# PowerManager.net
KiCad netlist of a schematic drawn in Altium Designer
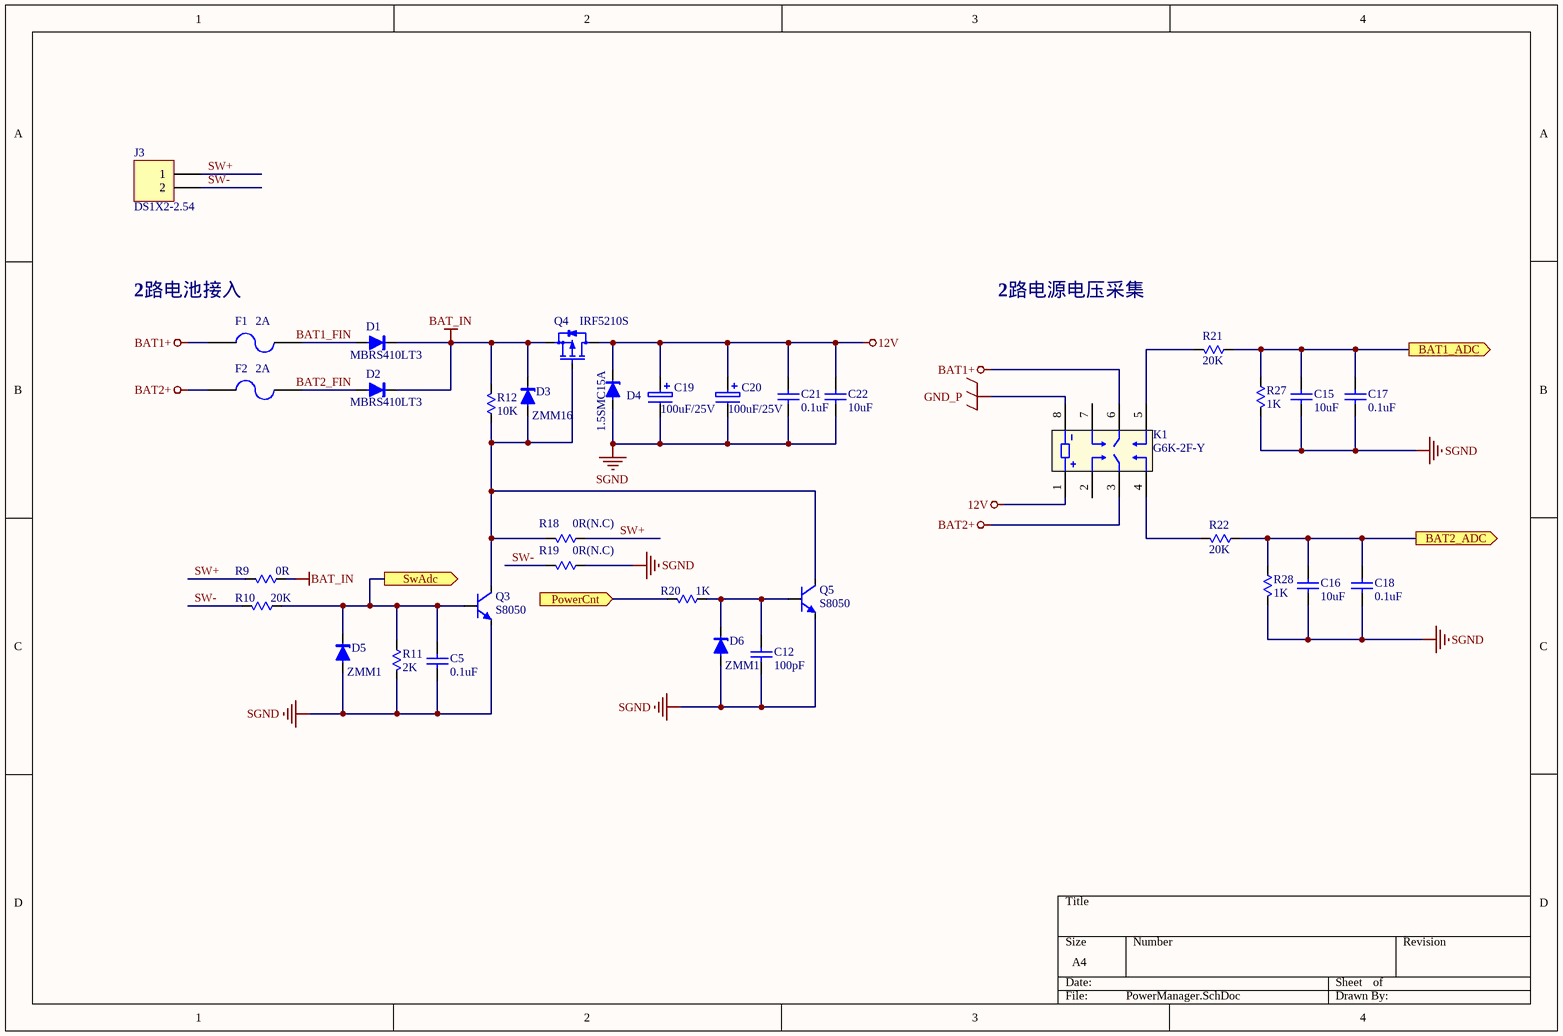
[diagram p0: PowerManager.SchDoc]

(export (version "E")
  (design (tool "Eeschema 10.0.6"))
  (components
    (comp (ref "C5")
      (value "0.1uF")
      (footprint "C0805")
      (description "Capacitor")
      (fields (field (name "PUBLISHER") "Altium Limited"))
      (libsource (lib "Miscellaneous Devices") (part "Cap"))
    )
    (comp (ref "C12")
      (value "100pF")
      (footprint "C0805")
      (description "Capacitor")
      (fields (field (name "PUBLISHER") "Altium Limited"))
      (libsource (lib "Miscellaneous Devices") (part "Cap"))
    )
    (comp (ref "C15")
      (value "10uF")
      (footprint "C0805")
      (description "CAP")
      (fields (field (name "PUBLISHER") "Altium Limited"))
      (libsource (lib "Passive Components Class") (part "CAP"))
    )
    (comp (ref "C16")
      (value "10uF")
      (footprint "C0805")
      (description "CAP")
      (fields (field (name "PUBLISHER") "Altium Limited"))
      (libsource (lib "Passive Components Class") (part "CAP"))
    )
    (comp (ref "C17")
      (value "0.1uF")
      (footprint "C0805")
      (description "CAP")
      (fields (field (name "PUBLISHER") "Altium Limited"))
      (libsource (lib "Passive Components Class") (part "CAP"))
    )
    (comp (ref "C18")
      (value "0.1uF")
      (footprint "C0805")
      (description "CAP")
      (fields (field (name "PUBLISHER") "Altium Limited"))
      (libsource (lib "Passive Components Class") (part "CAP"))
    )
    (comp (ref "C19")
      (value "100uF/25V")
      (footprint "CT7343-E-S")
      (description "Electrolytic Capacitor")
      (libsource (lib "*") (part "ELECTRO"))
    )
    (comp (ref "C20")
      (value "100uF/25V")
      (footprint "CT7343-E-S")
      (description "Electrolytic Capacitor")
      (libsource (lib "*") (part "ELECTRO"))
    )
    (comp (ref "C21")
      (value "0.1uF")
      (footprint "C0805")
      (description "Capacitor")
      (fields (field (name "PUBLISHER") "Altium Limited"))
      (libsource (lib "Miscellaneous Devices") (part "Cap"))
    )
    (comp (ref "C22")
      (value "10uF")
      (footprint "C0805")
      (description "Capacitor")
      (fields (field (name "PUBLISHER") "Altium Limited"))
      (libsource (lib "Miscellaneous Devices") (part "Cap"))
    )
    (comp (ref "D1")
      (value "MBRS410LT3")
      (footprint "SMC")
      (description "Small Signal Zener Diodes")
      (libsource (lib "Passive Components Class") (part "DIODE-ZENER"))
    )
    (comp (ref "D2")
      (value "MBRS410LT3")
      (footprint "SMC")
      (description "Small Signal Zener Diodes")
      (libsource (lib "Passive Components Class") (part "DIODE-ZENER"))
    )
    (comp (ref "D3")
      (value "ZMM16")
      (footprint "SOD-80")
      (description "Small Signal Zener Diodes")
      (libsource (lib "Passive Components Class") (part "DIODE-ZENER"))
    )
    (comp (ref "D4")
      (value "1.5SMC15A")
      (footprint "SMC")
      (description "Small Signal Zener Diodes")
      (libsource (lib "Passive Components Class") (part "DIODE-ZENER"))
    )
    (comp (ref "D5")
      (value "ZMM1")
      (footprint "SOD-80")
      (description "Small Signal Zener Diodes")
      (libsource (lib "Passive Components Class") (part "DIODE-ZENER"))
    )
    (comp (ref "D6")
      (value "ZMM1")
      (footprint "SOD-80")
      (description "Small Signal Zener Diodes")
      (libsource (lib "Passive Components Class") (part "DIODE-ZENER"))
    )
    (comp (ref "F1")
      (value "2A")
      (footprint "F1812")
      (description "Fuse")
      (libsource (lib "*") (part "FUSE2"))
    )
    (comp (ref "F2")
      (value "2A")
      (footprint "F1812")
      (description "Fuse")
      (libsource (lib "*") (part "FUSE2"))
    )
    (comp (ref "J3")
      (value "DS1X2-2.54")
      (footprint "ZH1X2WT-1.5")
      (description "Header, 2-Pin")
      (fields (field (name "PUBLISHER") "Altium Limited"))
      (libsource (lib "Miscellaneous Connectors") (part "Header 2"))
    )
    (comp (ref "K1")
      (value "G6K-2F-Y")
      (footprint "G6K-2F-Y")
      (libsource (lib "Productor Class") (part "G6K-2F-Y"))
    )
    (comp (ref "Q3")
      (value "S8050")
      (footprint "SOT-23")
      (description "NPN General Purpose Amplifier")
      (fields (field (name "PUBLISHER") "Altium Limited"))
      (libsource (lib "Bdmc4810") (part "NPN"))
    )
    (comp (ref "Q4")
      (value "IRF5210S")
      (footprint "TO-262")
      (description "P-Channel 30-V (D-S), 150 C MOSFET")
      (libsource (lib "Passive Components Class") (part "PMOS"))
    )
    (comp (ref "Q5")
      (value "S8050")
      (footprint "SOT-23")
      (description "NPN General Purpose Amplifier")
      (fields (field (name "PUBLISHER") "Altium Limited"))
      (libsource (lib "Bdmc4810") (part "NPN"))
    )
    (comp (ref "R9")
      (value "0R")
      (footprint "R0805")
      (description "Resistor")
      (fields (field (name "PUBLISHER") "Altium Limited"))
      (libsource (lib "Temp") (part "Res"))
    )
    (comp (ref "R10")
      (value "20K")
      (footprint "R0805")
      (description "Resistor")
      (fields (field (name "PUBLISHER") "Altium Limited"))
      (libsource (lib "Temp") (part "Res"))
    )
    (comp (ref "R11")
      (value "2K")
      (footprint "R0805")
      (description "Resistor")
      (fields (field (name "PUBLISHER") "Altium Limited"))
      (libsource (lib "Temp") (part "Res"))
    )
    (comp (ref "R12")
      (value "10K")
      (footprint "R0805")
      (description "Resistor")
      (fields (field (name "PUBLISHER") "Altium Limited"))
      (libsource (lib "Temp") (part "Res"))
    )
    (comp (ref "R18")
      (value "0R(N.C)")
      (footprint "R0805")
      (description "Resistor")
      (fields (field (name "PUBLISHER") "Altium Limited"))
      (libsource (lib "Passive Components Class") (part "RES"))
    )
    (comp (ref "R19")
      (value "0R(N.C)")
      (footprint "R0805")
      (description "Resistor")
      (fields (field (name "PUBLISHER") "Altium Limited"))
      (libsource (lib "Passive Components Class") (part "RES"))
    )
    (comp (ref "R20")
      (value "1K")
      (footprint "R0805")
      (description "Resistor")
      (fields (field (name "PUBLISHER") "Altium Limited"))
      (libsource (lib "Temp") (part "Res"))
    )
    (comp (ref "R21")
      (value "20K")
      (footprint "R0805")
      (description "Resistor")
      (fields (field (name "PUBLISHER") "Altium Limited"))
      (libsource (lib "") (part "RES_1"))
    )
    (comp (ref "R22")
      (value "20K")
      (footprint "R0805")
      (description "Resistor")
      (fields (field (name "PUBLISHER") "Altium Limited"))
      (libsource (lib "") (part "RES_1"))
    )
    (comp (ref "R27")
      (value "1K")
      (footprint "R0805")
      (description "Resistor")
      (fields (field (name "PUBLISHER") "Altium Limited"))
      (libsource (lib "") (part "RES_1"))
    )
    (comp (ref "R28")
      (value "1K")
      (footprint "R0805")
      (description "Resistor")
      (fields (field (name "PUBLISHER") "Altium Limited"))
      (libsource (lib "") (part "RES_1"))
    )
  )
  (nets
    (net (code "1") (name "/BAT1_ADC") (class "Default")
      (node (ref "C15") (pin "1") (pinfunction "1_1") (pintype "passive"))
      (node (ref "C17") (pin "1") (pinfunction "1_1") (pintype "passive"))
      (node (ref "R21") (pin "2") (pinfunction "2_2") (pintype "passive"))
      (node (ref "R27") (pin "2") (pinfunction "2_2") (pintype "passive"))
    )
    (net (code "3") (name "/BAT2_ADC") (class "Default")
      (node (ref "C16") (pin "1") (pinfunction "1_1") (pintype "passive"))
      (node (ref "C18") (pin "1") (pinfunction "1_1") (pintype "passive"))
      (node (ref "R22") (pin "2") (pinfunction "2_2") (pintype "passive"))
      (node (ref "R28") (pin "2") (pinfunction "2_2") (pintype "passive"))
    )
    (net (code "5") (name "/PowerCnt") (class "Default")
      (node (ref "R20") (pin "1") (pinfunction "1_1") (pintype "passive"))
    )
    (net (code "6") (name "/SW+") (class "Default")
      (node (ref "J3") (pin "1") (pinfunction "1_1") (pintype "passive"))
      (node (ref "R18") (pin "1") (pinfunction "1_1") (pintype "passive"))
      (node (ref "R9") (pin "1") (pinfunction "1_1") (pintype "passive"))
    )
    (net (code "7") (name "/SW-") (class "Default")
      (node (ref "J3") (pin "2") (pinfunction "2_2") (pintype "passive"))
      (node (ref "R10") (pin "1") (pinfunction "1_1") (pintype "passive"))
      (node (ref "R19") (pin "2") (pinfunction "2_2") (pintype "passive"))
    )
    (net (code "8") (name "/SwAdc") (class "Default")
      (node (ref "C5") (pin "2") (pinfunction "2_2") (pintype "passive"))
      (node (ref "D5") (pin "2") (pinfunction "K_2") (pintype "passive"))
      (node (ref "Q3") (pin "1") (pinfunction "B_1") (pintype "passive"))
      (node (ref "R10") (pin "2") (pinfunction "2_2") (pintype "passive"))
      (node (ref "R11") (pin "2") (pinfunction "2_2") (pintype "passive"))
    )
    (net (code "9") (name "12V") (class "Default")
      (node (ref "C19") (pin "1") (pinfunction "1_1") (pintype "passive"))
      (node (ref "C20") (pin "1") (pinfunction "1_1") (pintype "passive"))
      (node (ref "C21") (pin "2") (pinfunction "2_2") (pintype "passive"))
      (node (ref "C22") (pin "2") (pinfunction "2_2") (pintype "passive"))
      (node (ref "D4") (pin "2") (pinfunction "K_2") (pintype "passive"))
      (node (ref "K1") (pin "1") (pinfunction "1_1") (pintype "passive"))
      (node (ref "Q4") (pin "2") (pinfunction "D_2") (pintype "passive"))
    )
    (net (code "10") (name "BAT1+") (class "Default")
      (node (ref "F1") (pin "1") (pinfunction "1_1") (pintype "passive"))
      (node (ref "K1") (pin "6") (pinfunction "6_6") (pintype "passive"))
    )
    (net (code "11") (name "BAT2+") (class "Default")
      (node (ref "F2") (pin "1") (pinfunction "1_1") (pintype "passive"))
      (node (ref "K1") (pin "3") (pinfunction "3_3") (pintype "passive"))
    )
    (net (code "12") (name "BAT_IN") (class "Default")
      (node (ref "D1") (pin "2") (pinfunction "K_2") (pintype "passive"))
      (node (ref "D2") (pin "2") (pinfunction "K_2") (pintype "passive"))
      (node (ref "D3") (pin "2") (pinfunction "K_2") (pintype "passive"))
      (node (ref "Q4") (pin "3") (pinfunction "S_3") (pintype "passive"))
      (node (ref "R12") (pin "1") (pinfunction "1_1") (pintype "passive"))
      (node (ref "R9") (pin "2") (pinfunction "2_2") (pintype "passive"))
    )
    (net (code "13") (name "GND_P") (class "Default")
      (node (ref "K1") (pin "8") (pinfunction "8_8") (pintype "passive"))
    )
    (net (code "14") (name "Net-(D1-A)") (class "Default")
      (node (ref "D1") (pin "1") (pinfunction "A_1") (pintype "passive"))
      (node (ref "F1") (pin "2") (pinfunction "2_2") (pintype "passive"))
    )
    (net (code "15") (name "Net-(D2-A)") (class "Default")
      (node (ref "D2") (pin "1") (pinfunction "A_1") (pintype "passive"))
      (node (ref "F2") (pin "2") (pinfunction "2_2") (pintype "passive"))
    )
    (net (code "16") (name "Net-(D3-A)") (class "Default")
      (node (ref "D3") (pin "1") (pinfunction "A_1") (pintype "passive"))
      (node (ref "Q3") (pin "3") (pinfunction "C_3") (pintype "passive"))
      (node (ref "Q4") (pin "1") (pinfunction "G_1") (pintype "passive"))
      (node (ref "Q5") (pin "3") (pinfunction "C_3") (pintype "passive"))
      (node (ref "R12") (pin "2") (pinfunction "2_2") (pintype "passive"))
      (node (ref "R18") (pin "2") (pinfunction "2_2") (pintype "passive"))
    )
    (net (code "17") (name "Net-(D6-K)") (class "Default")
      (node (ref "C12") (pin "2") (pinfunction "2_2") (pintype "passive"))
      (node (ref "D6") (pin "2") (pinfunction "K_2") (pintype "passive"))
      (node (ref "Q5") (pin "1") (pinfunction "B_1") (pintype "passive"))
      (node (ref "R20") (pin "2") (pinfunction "2_2") (pintype "passive"))
    )
    (net (code "18") (name "Net-(K1-Pad4)") (class "Default")
      (node (ref "K1") (pin "4") (pinfunction "4_4") (pintype "passive"))
      (node (ref "R22") (pin "1") (pinfunction "1_1") (pintype "passive"))
    )
    (net (code "19") (name "Net-(K1-Pad5)") (class "Default")
      (node (ref "K1") (pin "5") (pinfunction "5_5") (pintype "passive"))
      (node (ref "R21") (pin "1") (pinfunction "1_1") (pintype "passive"))
    )
    (net (code "20") (name "SGND") (class "Default")
      (node (ref "C12") (pin "1") (pinfunction "1_1") (pintype "passive"))
      (node (ref "C15") (pin "2") (pinfunction "2_2") (pintype "passive"))
      (node (ref "C16") (pin "2") (pinfunction "2_2") (pintype "passive"))
      (node (ref "C17") (pin "2") (pinfunction "2_2") (pintype "passive"))
      (node (ref "C18") (pin "2") (pinfunction "2_2") (pintype "passive"))
      (node (ref "C19") (pin "2") (pinfunction "2_2") (pintype "passive"))
      (node (ref "C20") (pin "2") (pinfunction "2_2") (pintype "passive"))
      (node (ref "C21") (pin "1") (pinfunction "1_1") (pintype "passive"))
      (node (ref "C22") (pin "1") (pinfunction "1_1") (pintype "passive"))
      (node (ref "C5") (pin "1") (pinfunction "1_1") (pintype "passive"))
      (node (ref "D4") (pin "1") (pinfunction "A_1") (pintype "passive"))
      (node (ref "D5") (pin "1") (pinfunction "A_1") (pintype "passive"))
      (node (ref "D6") (pin "1") (pinfunction "A_1") (pintype "passive"))
      (node (ref "Q3") (pin "2") (pinfunction "E_2") (pintype "passive"))
      (node (ref "Q5") (pin "2") (pinfunction "E_2") (pintype "passive"))
      (node (ref "R11") (pin "1") (pinfunction "1_1") (pintype "passive"))
      (node (ref "R19") (pin "1") (pinfunction "1_1") (pintype "passive"))
      (node (ref "R27") (pin "1") (pinfunction "1_1") (pintype "passive"))
      (node (ref "R28") (pin "1") (pinfunction "1_1") (pintype "passive"))
    )
    (net (code "21") (name "unconnected-(K1-Pad2)") (class "Default")
      (node (ref "K1") (pin "2") (pinfunction "2_2") (pintype "passive"))
    )
    (net (code "22") (name "unconnected-(K1-Pad7)") (class "Default")
      (node (ref "K1") (pin "7") (pinfunction "7_7") (pintype "passive"))
    )
  )
)
